# Voltage_sensor_UVW.net
KiCad netlist of a schematic drawn in Altium Designer
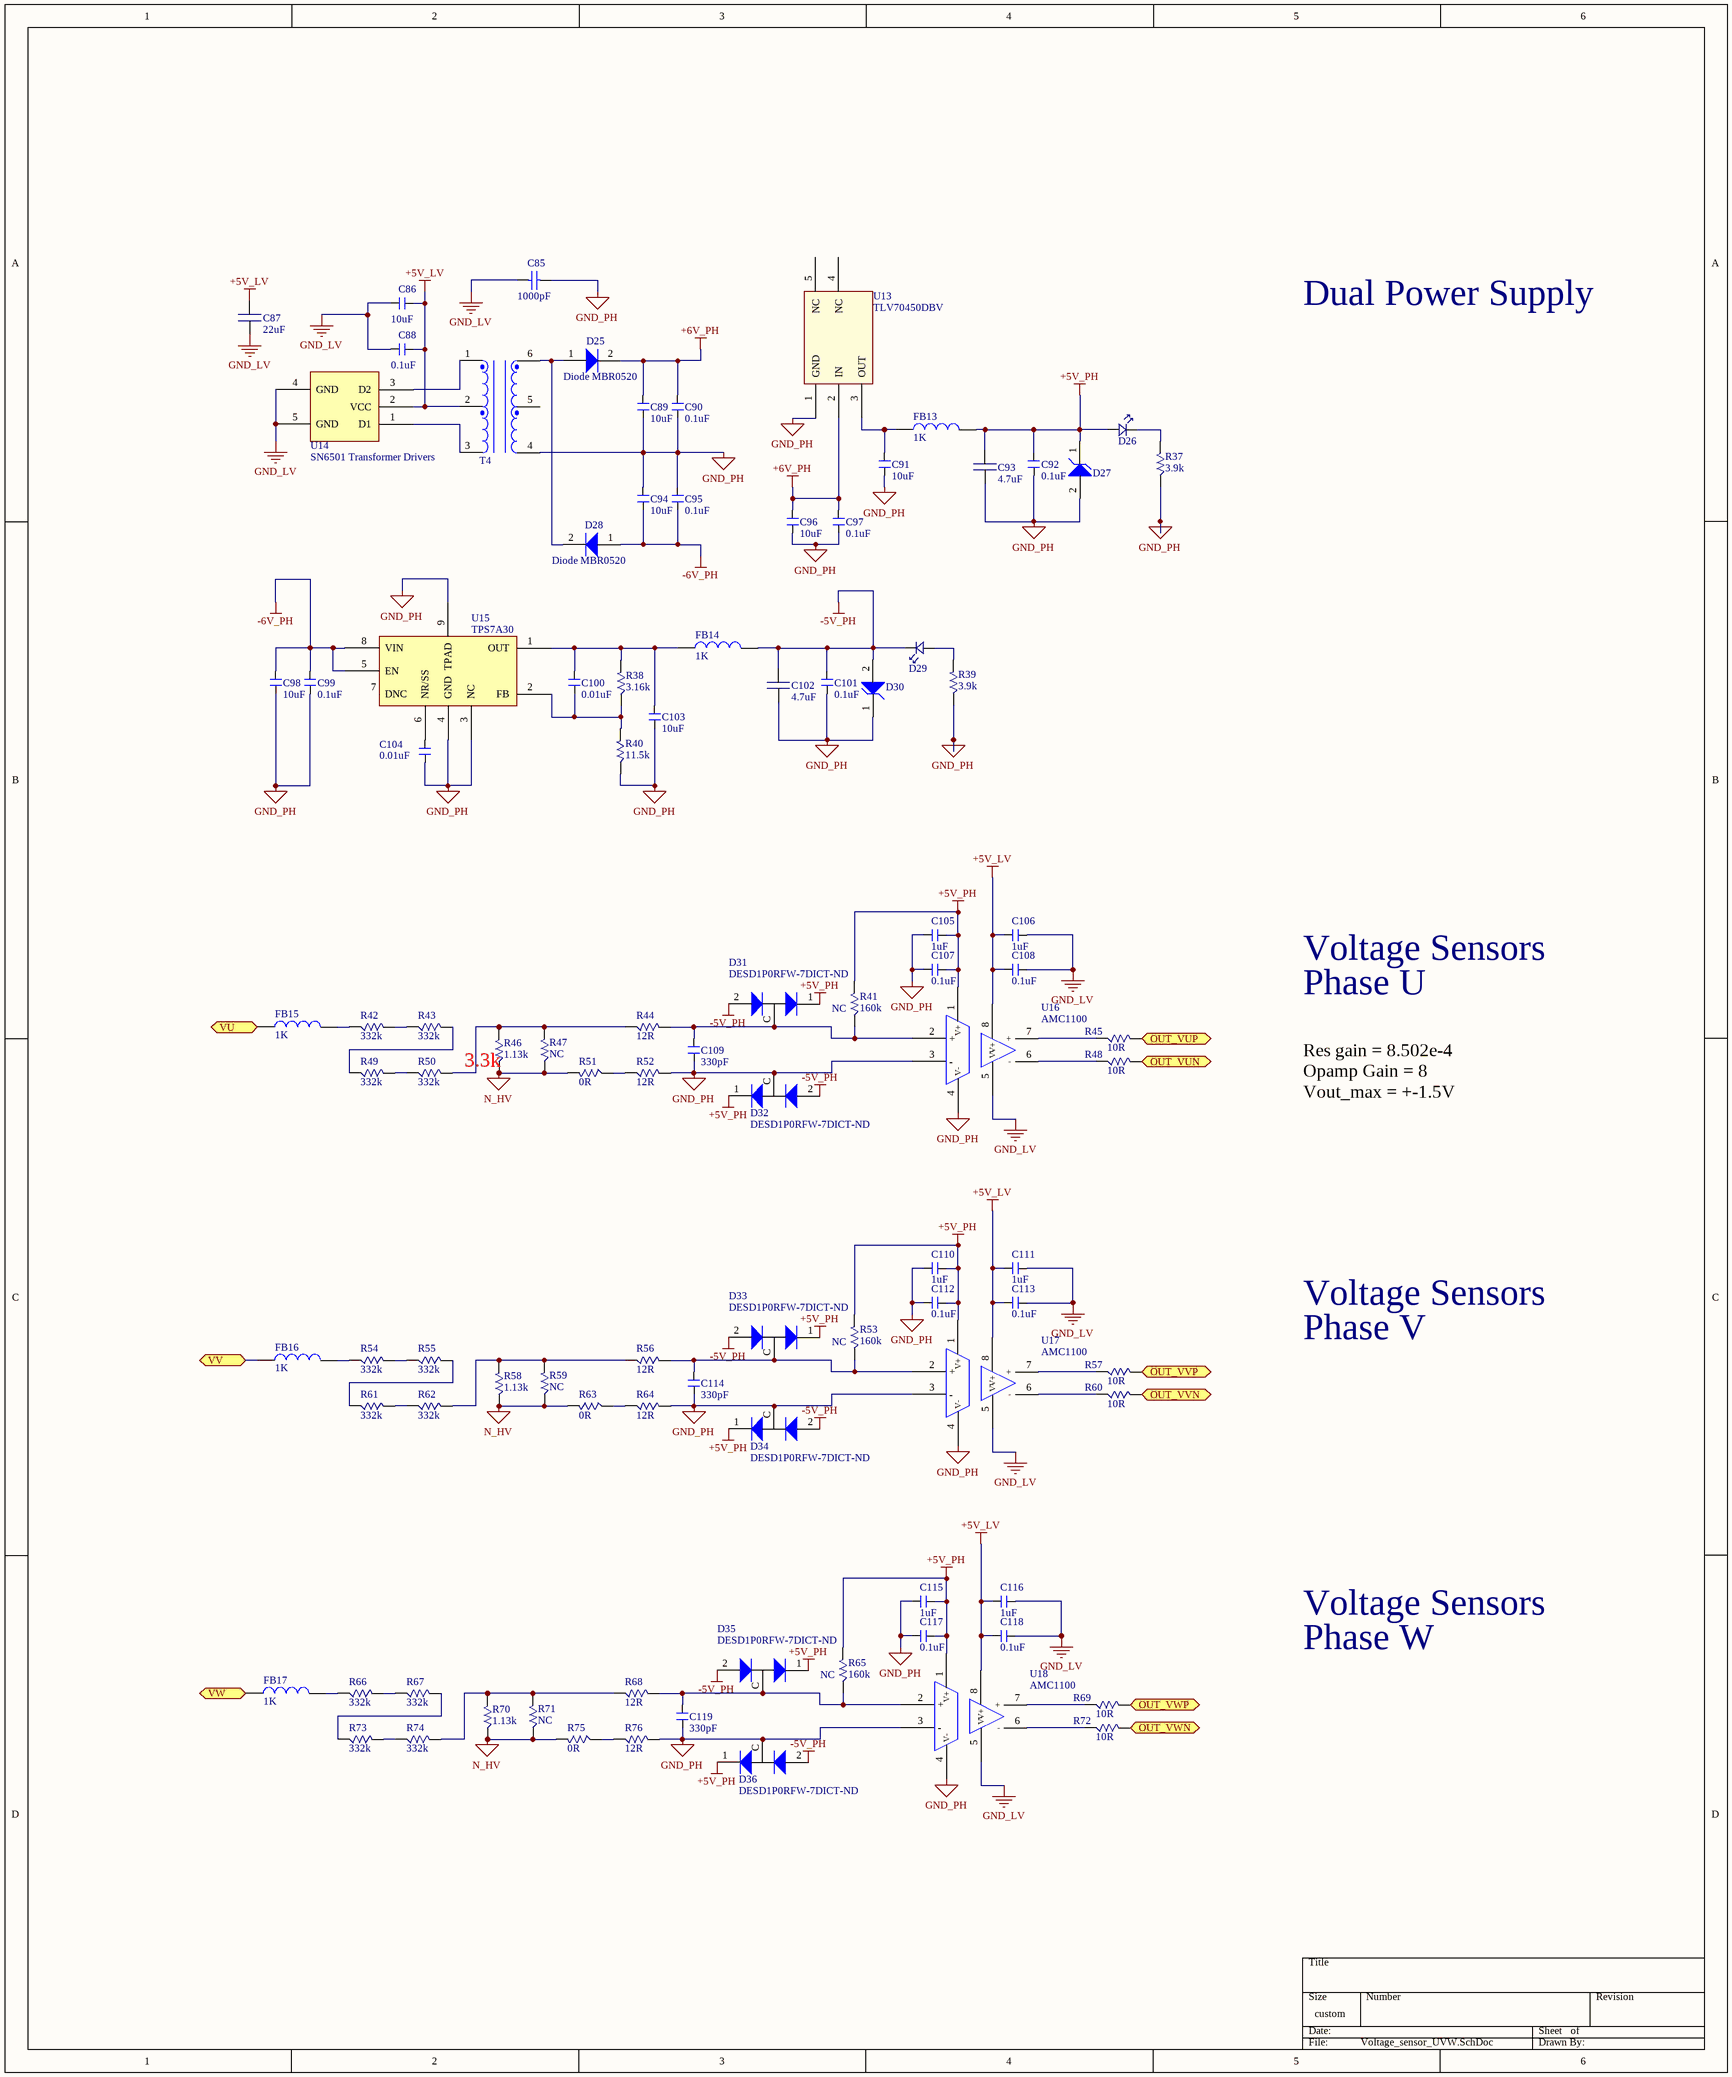
[diagram p0: Voltage_sensor_UVW.SchDoc]

(export (version "E")
  (design (tool "Eeschema 10.0.6"))
  (components
    (comp (ref "C85")
      (value "1000pF")
      (footprint "RAD-0.3")
      (description "CAP CER 1000PF 1KV Y5P RADIAL")
      (fields
        (field (name "PART") "1251PH-ND")
        (field (name "Comment") "Cap TH")
        (field (name "PUBLISHER") "Altium Limited")
      )
      (libsource (lib "Miscellaneous Devices") (part "Cap"))
    )
    (comp (ref "C86")
      (value "10uF")
      (footprint "0603 (1608 Metric)")
      (description "CAP CER 10UF 35V X5R 0805")
      (fields (field (name "PART") "490-10515-1-ND") (field (name "Comment") "Cap 0603_new"))
      (libsource (lib "Library_Microgrid") (part "Cap 0603_new"))
    )
    (comp (ref "C87")
      (value "22uF")
      (footprint "0805 (2012 metric)")
      (description "CAP CER 22UF 35V X5R 0805")
      (fields (field (name "PART") "445-14428-1-ND") (field (name "Comment") "Cap 0805"))
      (libsource (lib "Library_Microgrid") (part "Cap 0805"))
    )
    (comp (ref "C88")
      (value "0.1uF")
      (footprint "0603 (1608 Metric)")
      (description "CAP CER 0.1UF 50V Y5V 0603")
      (fields (field (name "PART") "311-1343-6-ND") (field (name "Comment") "Cap 0603_new"))
      (libsource (lib "Library_Microgrid") (part "Cap 0603_new"))
    )
    (comp (ref "C89")
      (value "10uF")
      (footprint "0603 (1608 Metric)")
      (description "CAP CER 10UF 35V X5R 0805")
      (fields (field (name "PART") "490-10515-1-ND") (field (name "Comment") "Cap 0603_new"))
      (libsource (lib "Library_Microgrid") (part "Cap 0603_new"))
    )
    (comp (ref "C90")
      (value "0.1uF")
      (footprint "0603 (1608 Metric)")
      (description "CAP CER 0.1UF 50V Y5V 0603")
      (fields (field (name "PART") "311-1343-6-ND") (field (name "Comment") "Cap 0603_new"))
      (libsource (lib "Library_Microgrid") (part "Cap 0603_new"))
    )
    (comp (ref "C91")
      (value "10uF")
      (footprint "0603 (1608 Metric)")
      (description "CAP CER 10UF 35V X5R 0805")
      (fields (field (name "PART") "490-10515-1-ND") (field (name "Comment") "Cap 0603_new"))
      (libsource (lib "Library_Microgrid") (part "Cap 0603_new"))
    )
    (comp (ref "C92")
      (value "0.1uF")
      (footprint "0603 (1608 Metric)")
      (description "CAP CER 0.1UF 50V Y5V 0603")
      (fields (field (name "PART") "311-1343-6-ND") (field (name "Comment") "Cap 0603_new"))
      (libsource (lib "Library_Microgrid") (part "Cap 0603_new"))
    )
    (comp (ref "C93")
      (value "4.7uF")
      (footprint "0805 (2012 metric)")
      (description "CAP CER 4.7UF 50V X5R 0805")
      (fields (field (name "PART") "445-5980-1-ND") (field (name "Comment") "Cap 0805"))
      (libsource (lib "Library_Microgrid") (part "Cap 0805"))
    )
    (comp (ref "C94")
      (value "10uF")
      (footprint "0603 (1608 Metric)")
      (description "CAP CER 10UF 35V X5R 0805")
      (fields (field (name "PART") "490-10515-1-ND") (field (name "Comment") "Cap 0603_new"))
      (libsource (lib "Library_Microgrid") (part "Cap 0603_new"))
    )
    (comp (ref "C95")
      (value "0.1uF")
      (footprint "0603 (1608 Metric)")
      (description "CAP CER 0.1UF 50V Y5V 0603")
      (fields (field (name "PART") "311-1343-6-ND") (field (name "Comment") "Cap 0603_new"))
      (libsource (lib "Library_Microgrid") (part "Cap 0603_new"))
    )
    (comp (ref "C96")
      (value "10uF")
      (footprint "0603 (1608 Metric)")
      (description "CAP CER 10UF 35V X5R 0805")
      (fields (field (name "PART") "490-10515-1-ND") (field (name "Comment") "Cap 0603_new"))
      (libsource (lib "Library_Microgrid") (part "Cap 0603_new"))
    )
    (comp (ref "C97")
      (value "0.1uF")
      (footprint "0603 (1608 Metric)")
      (description "CAP CER 0.1UF 50V Y5V 0603")
      (fields (field (name "PART") "311-1343-6-ND") (field (name "Comment") "Cap 0603_new"))
      (libsource (lib "Library_Microgrid") (part "Cap 0603_new"))
    )
    (comp (ref "C98")
      (value "10uF")
      (footprint "0603 (1608 Metric)")
      (description "CAP CER 10UF 35V X5R 0805")
      (fields (field (name "PART") "490-10515-1-ND") (field (name "Comment") "Cap 0603_new"))
      (libsource (lib "Library_Microgrid") (part "Cap 0603_new"))
    )
    (comp (ref "C99")
      (value "0.1uF")
      (footprint "0603 (1608 Metric)")
      (description "CAP CER 0.1UF 50V Y5V 0603")
      (fields (field (name "PART") "311-1343-6-ND") (field (name "Comment") "Cap 0603_new"))
      (libsource (lib "Library_Microgrid") (part "Cap 0603_new"))
    )
    (comp (ref "C100")
      (value "0.01uF")
      (footprint "0603 (1608 Metric)")
      (description "CAP CER 10000PF 100V X7R 0603")
      (fields (field (name "PART") "478-7418-1-ND") (field (name "Comment") "Cap 0603_new"))
      (libsource (lib "Library_Microgrid") (part "Cap 0603_new"))
    )
    (comp (ref "C101")
      (value "0.1uF")
      (footprint "0603 (1608 Metric)")
      (description "CAP CER 0.1UF 50V Y5V 0603")
      (fields (field (name "PART") "311-1343-6-ND") (field (name "Comment") "Cap 0603_new"))
      (libsource (lib "Library_Microgrid") (part "Cap 0603_new"))
    )
    (comp (ref "C102")
      (value "4.7uF")
      (footprint "0805 (2012 metric)")
      (description "CAP CER 4.7UF 50V X5R 0805")
      (fields (field (name "PART") "445-5980-1-ND") (field (name "Comment") "Cap 0805"))
      (libsource (lib "Library_Microgrid") (part "Cap 0805"))
    )
    (comp (ref "C103")
      (value "10uF")
      (footprint "0603 (1608 Metric)")
      (description "CAP CER 10UF 35V X5R 0805")
      (fields (field (name "PART") "490-10515-1-ND") (field (name "Comment") "Cap 0603_new"))
      (libsource (lib "Library_Microgrid") (part "Cap 0603_new"))
    )
    (comp (ref "C104")
      (value "0.01uF")
      (footprint "0603 (1608 Metric)")
      (description "CAP CER 10000PF 100V X7R 0603")
      (fields (field (name "PART") "478-7418-1-ND") (field (name "Comment") "Cap 0603_new"))
      (libsource (lib "Library_Microgrid") (part "Cap 0603_new"))
    )
    (comp (ref "C105")
      (value "1uF")
      (footprint "0603 (1608 Metric)")
      (description "CAP CER 1UF 50V X5R 0603")
      (fields (field (name "PART") "1276-1860-1-ND") (field (name "Comment") "Cap 0603_new"))
      (libsource (lib "Library_Microgrid") (part "Cap 0603_new"))
    )
    (comp (ref "C106")
      (value "1uF")
      (footprint "0603 (1608 Metric)")
      (description "CAP CER 1UF 50V X5R 0603")
      (fields (field (name "PART") "1276-1860-1-ND") (field (name "Comment") "Cap 0603_new"))
      (libsource (lib "Library_Microgrid") (part "Cap 0603_new"))
    )
    (comp (ref "C107")
      (value "0.1uF")
      (footprint "0603 (1608 Metric)")
      (description "CAP CER 0.1UF 50V Y5V 0603")
      (fields (field (name "PART") "311-1343-6-ND") (field (name "Comment") "Cap 0603_new"))
      (libsource (lib "Library_Microgrid") (part "Cap 0603_new"))
    )
    (comp (ref "C108")
      (value "0.1uF")
      (footprint "0603 (1608 Metric)")
      (description "CAP CER 0.1UF 50V Y5V 0603")
      (fields (field (name "PART") "311-1343-6-ND") (field (name "Comment") "Cap 0603_new"))
      (libsource (lib "Library_Microgrid") (part "Cap 0603_new"))
    )
    (comp (ref "C109")
      (value "330pF")
      (footprint "0603 (1608 Metric)")
      (description "CAP CER 330PF 50V C0G 0603")
      (fields (field (name "PART") "445-7033-2-ND") (field (name "Comment") "Cap 0603_new"))
      (libsource (lib "Library_Microgrid") (part "Cap 0603_new"))
    )
    (comp (ref "C110")
      (value "1uF")
      (footprint "0603 (1608 Metric)")
      (description "CAP CER 1UF 50V X5R 0603")
      (fields (field (name "PART") "1276-1860-1-ND") (field (name "Comment") "Cap 0603_new"))
      (libsource (lib "Library_Microgrid") (part "Cap 0603_new"))
    )
    (comp (ref "C111")
      (value "1uF")
      (footprint "0603 (1608 Metric)")
      (description "CAP CER 1UF 50V X5R 0603")
      (fields (field (name "PART") "1276-1860-1-ND") (field (name "Comment") "Cap 0603_new"))
      (libsource (lib "Library_Microgrid") (part "Cap 0603_new"))
    )
    (comp (ref "C112")
      (value "0.1uF")
      (footprint "0603 (1608 Metric)")
      (description "CAP CER 0.1UF 50V Y5V 0603")
      (fields (field (name "PART") "311-1343-6-ND") (field (name "Comment") "Cap 0603_new"))
      (libsource (lib "Library_Microgrid") (part "Cap 0603_new"))
    )
    (comp (ref "C113")
      (value "0.1uF")
      (footprint "0603 (1608 Metric)")
      (description "CAP CER 0.1UF 50V Y5V 0603")
      (fields (field (name "PART") "311-1343-6-ND") (field (name "Comment") "Cap 0603_new"))
      (libsource (lib "Library_Microgrid") (part "Cap 0603_new"))
    )
    (comp (ref "C114")
      (value "330pF")
      (footprint "0603 (1608 Metric)")
      (description "CAP CER 330PF 50V C0G 0603")
      (fields (field (name "PART") "445-7033-2-ND") (field (name "Comment") "Cap 0603_new"))
      (libsource (lib "Library_Microgrid") (part "Cap 0603_new"))
    )
    (comp (ref "C115")
      (value "1uF")
      (footprint "0603 (1608 Metric)")
      (description "CAP CER 1UF 50V X5R 0603")
      (fields (field (name "PART") "1276-1860-1-ND") (field (name "Comment") "Cap 0603_new"))
      (libsource (lib "Library_Microgrid") (part "Cap 0603_new"))
    )
    (comp (ref "C116")
      (value "1uF")
      (footprint "0603 (1608 Metric)")
      (description "CAP CER 1UF 50V X5R 0603")
      (fields (field (name "PART") "1276-1860-1-ND") (field (name "Comment") "Cap 0603_new"))
      (libsource (lib "Library_Microgrid") (part "Cap 0603_new"))
    )
    (comp (ref "C117")
      (value "0.1uF")
      (footprint "0603 (1608 Metric)")
      (description "CAP CER 0.1UF 50V Y5V 0603")
      (fields (field (name "PART") "311-1343-6-ND") (field (name "Comment") "Cap 0603_new"))
      (libsource (lib "Library_Microgrid") (part "Cap 0603_new"))
    )
    (comp (ref "C118")
      (value "0.1uF")
      (footprint "0603 (1608 Metric)")
      (description "CAP CER 0.1UF 50V Y5V 0603")
      (fields (field (name "PART") "311-1343-6-ND") (field (name "Comment") "Cap 0603_new"))
      (libsource (lib "Library_Microgrid") (part "Cap 0603_new"))
    )
    (comp (ref "C119")
      (value "330pF")
      (footprint "0603 (1608 Metric)")
      (description "CAP CER 330PF 50V C0G 0603")
      (fields (field (name "PART") "445-7033-2-ND") (field (name "Comment") "Cap 0603_new"))
      (libsource (lib "Library_Microgrid") (part "Cap 0603_new"))
    )
    (comp (ref "D25")
      (value "Diode MBR0520")
      (footprint "SOD-123")
      (description "DIODE SCHOTTKY 20V 500MA SOD123")
      (fields (field (name "PART") "MBR0520LT1GOSCT-ND"))
      (libsource (lib "Library_Microgrid") (part "Diode MBR0520"))
    )
    (comp (ref "D26")
      (value "LED")
      (footprint "0805 (2012 Metric) Diode")
      (description "LED 0805")
      (libsource (lib "Library_Microgrid") (part "LED"))
    )
    (comp (ref "D27")
      (value "*")
      (footprint "POWERDI")
      (description "DIODE ZENER POWERDI123")
      (fields (field (name "PART") "MMSZ5228B-FDICT-ND"))
      (libsource (lib "Library_Microgrid") (part "Diode Zener POWERDI123"))
    )
    (comp (ref "D28")
      (value "Diode MBR0520")
      (footprint "SOD-123")
      (description "DIODE SCHOTTKY 20V 500MA SOD123")
      (fields (field (name "PART") "MBR0520LT1GOSCT-ND"))
      (libsource (lib "Library_Microgrid") (part "Diode MBR0520"))
    )
    (comp (ref "D29")
      (value "LED")
      (footprint "0805 (2012 Metric) Diode")
      (description "LED 0805")
      (libsource (lib "Library_Microgrid") (part "LED"))
    )
    (comp (ref "D30")
      (value "*")
      (footprint "POWERDI")
      (description "DIODE ZENER POWERDI123")
      (fields (field (name "PART") "MMSZ5228B-FDICT-ND"))
      (libsource (lib "Library_Microgrid") (part "Diode Zener POWERDI123"))
    )
    (comp (ref "D31")
      (value "TVS - Diodes")
      (footprint "SOT323_ESD")
      (description "TVS DIODE 70VWM 8VC SOT323")
      (fields (field (name "PART") "DESD1P0RFW-7DICT-ND"))
      (libsource (lib "Library_Microgrid") (part "Diode_ESD"))
    )
    (comp (ref "D32")
      (value "TVS - Diodes")
      (footprint "SOT323_ESD")
      (description "TVS DIODE 70VWM 8VC SOT323")
      (fields (field (name "PART") "DESD1P0RFW-7DICT-ND"))
      (libsource (lib "Library_Microgrid") (part "Diode_ESD"))
    )
    (comp (ref "D33")
      (value "TVS - Diodes")
      (footprint "SOT323_ESD")
      (description "TVS DIODE 70VWM 8VC SOT323")
      (fields (field (name "PART") "DESD1P0RFW-7DICT-ND"))
      (libsource (lib "Library_Microgrid") (part "Diode_ESD"))
    )
    (comp (ref "D34")
      (value "TVS - Diodes")
      (footprint "SOT323_ESD")
      (description "TVS DIODE 70VWM 8VC SOT323")
      (fields (field (name "PART") "DESD1P0RFW-7DICT-ND"))
      (libsource (lib "Library_Microgrid") (part "Diode_ESD"))
    )
    (comp (ref "D35")
      (value "TVS - Diodes")
      (footprint "SOT323_ESD")
      (description "TVS DIODE 70VWM 8VC SOT323")
      (fields (field (name "PART") "DESD1P0RFW-7DICT-ND"))
      (libsource (lib "Library_Microgrid") (part "Diode_ESD"))
    )
    (comp (ref "D36")
      (value "TVS - Diodes")
      (footprint "SOT323_ESD")
      (description "TVS DIODE 70VWM 8VC SOT323")
      (fields (field (name "PART") "DESD1P0RFW-7DICT-ND"))
      (libsource (lib "Library_Microgrid") (part "Diode_ESD"))
    )
    (comp (ref "FB13")
      (value "1K")
      (footprint "0603 (1608 Metric)")
      (description "FERRITE BEAD 1 KOHM 0603 1LN")
      (fields (field (name "PART") "445-8672-1-ND") (field (name "Comment") "Ferrite bead"))
      (libsource (lib "Library_Microgrid") (part "Ferrite bead"))
    )
    (comp (ref "FB14")
      (value "1K")
      (footprint "0603 (1608 Metric)")
      (description "FERRITE BEAD 1 KOHM 0603 1LN")
      (fields (field (name "PART") "445-8672-1-ND") (field (name "Comment") "Ferrite bead"))
      (libsource (lib "Library_Microgrid") (part "Ferrite bead"))
    )
    (comp (ref "FB15")
      (value "1K")
      (footprint "0603 (1608 Metric)")
      (description "FERRITE BEAD 1 KOHM 0603 1LN")
      (fields (field (name "PART") "445-8672-1-ND") (field (name "Comment") "Ferrite bead"))
      (libsource (lib "Library_Microgrid") (part "Ferrite bead"))
    )
    (comp (ref "FB16")
      (value "1K")
      (footprint "0603 (1608 Metric)")
      (description "FERRITE BEAD 1 KOHM 0603 1LN")
      (fields (field (name "PART") "445-8672-1-ND") (field (name "Comment") "Ferrite bead"))
      (libsource (lib "Library_Microgrid") (part "Ferrite bead"))
    )
    (comp (ref "FB17")
      (value "1K")
      (footprint "0603 (1608 Metric)")
      (description "FERRITE BEAD 1 KOHM 0603 1LN")
      (fields (field (name "PART") "445-8672-1-ND") (field (name "Comment") "Ferrite bead"))
      (libsource (lib "Library_Microgrid") (part "Ferrite bead"))
    )
    (comp (ref "R37")
      (value "3.9k")
      (footprint "0603 (1608 Metric)")
      (description "RES SMD 3.9K OHM 5% 1/10W 0603")
      (fields (field (name "PART") "541-3.9KGCT-ND") (field (name "Comment") "Resistor 0603"))
      (libsource (lib "Library_Microgrid") (part "Resistor 0603"))
    )
    (comp (ref "R38")
      (value "3.16k")
      (footprint "0603 (1608 Metric)")
      (description "RES SMD 3.16K OHM 1% 1/10W 0603")
      (fields (field (name "PART") "311-3.16KHRCT-ND") (field (name "Comment") "Resistor 0603"))
      (libsource (lib "Library_Microgrid") (part "Resistor 0603"))
    )
    (comp (ref "R39")
      (value "3.9k")
      (footprint "0603 (1608 Metric)")
      (description "RES SMD 3.9K OHM 5% 1/10W 0603")
      (fields (field (name "PART") "541-3.9KGCT-ND") (field (name "Comment") "Resistor 0603"))
      (libsource (lib "Library_Microgrid") (part "Resistor 0603"))
    )
    (comp (ref "R40")
      (value "11.5k")
      (footprint "0603 (1608 Metric)")
      (description "RES SMD 11.5K OHM 1% 1/10W 0603")
      (fields (field (name "PART") "541-11.5KHCT-ND") (field (name "Comment") "Resistor 0603"))
      (libsource (lib "Library_Microgrid") (part "Resistor 0603"))
    )
    (comp (ref "R41")
      (value "NC")
      (footprint "0603 (1608 Metric)")
      (description "Resistor 0603")
      (fields (field (name "ALTIUM_VALUE") "160k"))
      (libsource (lib "Library_Microgrid") (part "Resistor 0603"))
    )
    (comp (ref "R42")
      (value "332k")
      (footprint "1206")
      (description "RES SMD 332K OHM 0.1% 1/4W 1206")
      (fields (field (name "PART") "RG32P332KBCT-ND") (field (name "Comment") "Resistor 1206"))
      (libsource (lib "Library_Microgrid") (part "Resistor 1206"))
    )
    (comp (ref "R43")
      (value "332k")
      (footprint "1206")
      (description "RES SMD 332K OHM 0.1% 1/4W 1206")
      (fields (field (name "PART") "RG32P332KBCT-ND") (field (name "Comment") "Resistor 1206"))
      (libsource (lib "Library_Microgrid") (part "Resistor 1206"))
    )
    (comp (ref "R44")
      (value "12R")
      (footprint "1206")
      (description "12 Ohm ±0.5% 0.25W, 1/4W Chip Resistor 1206")
      (fields (field (name "PART") "311-2961-1-ND") (field (name "Comment") "Resistor 1206"))
      (libsource (lib "Library_Microgrid") (part "Resistor 1206"))
    )
    (comp (ref "R45")
      (value "10R")
      (footprint "0603 (1608 Metric)")
      (description "RES SMD 10 OHM 0.05% 1/10W 0603")
      (fields (field (name "PART") "RNCF0603AKT10R0CT-ND") (field (name "Comment") "Resistor 0603"))
      (libsource (lib "Library_Microgrid") (part "Resistor 0603"))
    )
    (comp (ref "R46")
      (value "1.13k")
      (footprint "1206")
      (description "RES SMD 1.13K OHM 0.1% 1/4W 1206")
      (fields (field (name "PART") "P1.13KBCCT-ND") (field (name "Comment") "Resistor 1206"))
      (libsource (lib "Library_Microgrid") (part "Resistor 1206"))
    )
    (comp (ref "R47")
      (value "NC")
      (footprint "1206")
      (fields (field (name "Comment") "Resistor 1206"))
      (libsource (lib "Library_Microgrid") (part "Resistor 1206"))
    )
    (comp (ref "R48")
      (value "10R")
      (footprint "0603 (1608 Metric)")
      (description "RES SMD 10 OHM 0.05% 1/10W 0603")
      (fields (field (name "PART") "RNCF0603AKT10R0CT-ND") (field (name "Comment") "Resistor 0603"))
      (libsource (lib "Library_Microgrid") (part "Resistor 0603"))
    )
    (comp (ref "R49")
      (value "332k")
      (footprint "1206")
      (description "RES SMD 332K OHM 0.1% 1/4W 1206")
      (fields (field (name "PART") "RG32P332KBCT-ND") (field (name "Comment") "Resistor 1206"))
      (libsource (lib "Library_Microgrid") (part "Resistor 1206"))
    )
    (comp (ref "R50")
      (value "332k")
      (footprint "1206")
      (description "RES SMD 332K OHM 0.1% 1/4W 1206")
      (fields (field (name "PART") "RG32P332KBCT-ND") (field (name "Comment") "Resistor 1206"))
      (libsource (lib "Library_Microgrid") (part "Resistor 1206"))
    )
    (comp (ref "R51")
      (value "0R")
      (footprint "0603 (1608 Metric)")
      (fields (field (name "Comment") "Resistor 0603"))
      (libsource (lib "Library_Microgrid") (part "Resistor 0603"))
    )
    (comp (ref "R52")
      (value "12R")
      (footprint "1206")
      (description "12 Ohm ±0.5% 0.25W, 1/4W Chip Resistor 1206")
      (fields (field (name "PART") "311-2961-1-ND") (field (name "Comment") "Resistor 1206"))
      (libsource (lib "Library_Microgrid") (part "Resistor 1206"))
    )
    (comp (ref "R53")
      (value "NC")
      (footprint "0603 (1608 Metric)")
      (description "Resistor 0603")
      (fields (field (name "ALTIUM_VALUE") "160k"))
      (libsource (lib "Library_Microgrid") (part "Resistor 0603"))
    )
    (comp (ref "R54")
      (value "332k")
      (footprint "1206")
      (description "RES SMD 332K OHM 0.1% 1/4W 1206")
      (fields (field (name "PART") "RG32P332KBCT-ND") (field (name "Comment") "Resistor 1206"))
      (libsource (lib "Library_Microgrid") (part "Resistor 1206"))
    )
    (comp (ref "R55")
      (value "332k")
      (footprint "1206")
      (description "RES SMD 332K OHM 0.1% 1/4W 1206")
      (fields (field (name "PART") "RG32P332KBCT-ND") (field (name "Comment") "Resistor 1206"))
      (libsource (lib "Library_Microgrid") (part "Resistor 1206"))
    )
    (comp (ref "R56")
      (value "12R")
      (footprint "1206")
      (description "12 Ohm ±0.5% 0.25W, 1/4W Chip Resistor 1206")
      (fields (field (name "PART") "311-2961-1-ND") (field (name "Comment") "Resistor 1206"))
      (libsource (lib "Library_Microgrid") (part "Resistor 1206"))
    )
    (comp (ref "R57")
      (value "10R")
      (footprint "0603 (1608 Metric)")
      (description "RES SMD 10 OHM 0.05% 1/10W 0603")
      (fields (field (name "PART") "RNCF0603AKT10R0CT-ND") (field (name "Comment") "Resistor 0603"))
      (libsource (lib "Library_Microgrid") (part "Resistor 0603"))
    )
    (comp (ref "R58")
      (value "1.13k")
      (footprint "1206")
      (description "RES SMD 1.13K OHM 0.1% 1/4W 1206")
      (fields (field (name "PART") "P1.13KBCCT-ND") (field (name "Comment") "Resistor 1206"))
      (libsource (lib "Library_Microgrid") (part "Resistor 1206"))
    )
    (comp (ref "R59")
      (value "NC")
      (footprint "1206")
      (fields (field (name "Comment") "Resistor 1206"))
      (libsource (lib "Library_Microgrid") (part "Resistor 1206"))
    )
    (comp (ref "R60")
      (value "10R")
      (footprint "0603 (1608 Metric)")
      (description "RES SMD 10 OHM 0.05% 1/10W 0603")
      (fields (field (name "PART") "RNCF0603AKT10R0CT-ND") (field (name "Comment") "Resistor 0603"))
      (libsource (lib "Library_Microgrid") (part "Resistor 0603"))
    )
    (comp (ref "R61")
      (value "332k")
      (footprint "1206")
      (description "RES SMD 332K OHM 0.1% 1/4W 1206")
      (fields (field (name "PART") "RG32P332KBCT-ND") (field (name "Comment") "Resistor 1206"))
      (libsource (lib "Library_Microgrid") (part "Resistor 1206"))
    )
    (comp (ref "R62")
      (value "332k")
      (footprint "1206")
      (description "RES SMD 332K OHM 0.1% 1/4W 1206")
      (fields (field (name "PART") "RG32P332KBCT-ND") (field (name "Comment") "Resistor 1206"))
      (libsource (lib "Library_Microgrid") (part "Resistor 1206"))
    )
    (comp (ref "R63")
      (value "0R")
      (footprint "0603 (1608 Metric)")
      (fields (field (name "Comment") "Resistor 0603"))
      (libsource (lib "Library_Microgrid") (part "Resistor 0603"))
    )
    (comp (ref "R64")
      (value "12R")
      (footprint "1206")
      (description "12 Ohm ±0.5% 0.25W, 1/4W Chip Resistor 1206")
      (fields (field (name "PART") "311-2961-1-ND") (field (name "Comment") "Resistor 1206"))
      (libsource (lib "Library_Microgrid") (part "Resistor 1206"))
    )
    (comp (ref "R65")
      (value "NC")
      (footprint "0603 (1608 Metric)")
      (description "Resistor 0603")
      (fields (field (name "ALTIUM_VALUE") "160k"))
      (libsource (lib "Library_Microgrid") (part "Resistor 0603"))
    )
    (comp (ref "R66")
      (value "332k")
      (footprint "1206")
      (description "RES SMD 332K OHM 0.1% 1/4W 1206")
      (fields (field (name "PART") "RG32P332KBCT-ND") (field (name "Comment") "Resistor 1206"))
      (libsource (lib "Library_Microgrid") (part "Resistor 1206"))
    )
    (comp (ref "R67")
      (value "332k")
      (footprint "1206")
      (description "RES SMD 332K OHM 0.1% 1/4W 1206")
      (fields (field (name "PART") "RG32P332KBCT-ND") (field (name "Comment") "Resistor 1206"))
      (libsource (lib "Library_Microgrid") (part "Resistor 1206"))
    )
    (comp (ref "R68")
      (value "12R")
      (footprint "1206")
      (description "12 Ohm ±0.5% 0.25W, 1/4W Chip Resistor 1206")
      (fields (field (name "PART") "311-2961-1-ND") (field (name "Comment") "Resistor 1206"))
      (libsource (lib "Library_Microgrid") (part "Resistor 1206"))
    )
    (comp (ref "R69")
      (value "10R")
      (footprint "0603 (1608 Metric)")
      (description "RES SMD 10 OHM 0.05% 1/10W 0603")
      (fields (field (name "PART") "RNCF0603AKT10R0CT-ND") (field (name "Comment") "Resistor 0603"))
      (libsource (lib "Library_Microgrid") (part "Resistor 0603"))
    )
    (comp (ref "R70")
      (value "1.13k")
      (footprint "1206")
      (description "RES SMD 1.13K OHM 0.1% 1/4W 1206")
      (fields (field (name "PART") "P1.13KBCCT-ND") (field (name "Comment") "Resistor 1206"))
      (libsource (lib "Library_Microgrid") (part "Resistor 1206"))
    )
    (comp (ref "R71")
      (value "NC")
      (footprint "1206")
      (fields (field (name "Comment") "Resistor 1206"))
      (libsource (lib "Library_Microgrid") (part "Resistor 1206"))
    )
    (comp (ref "R72")
      (value "10R")
      (footprint "0603 (1608 Metric)")
      (description "RES SMD 10 OHM 0.05% 1/10W 0603")
      (fields (field (name "PART") "RNCF0603AKT10R0CT-ND") (field (name "Comment") "Resistor 0603"))
      (libsource (lib "Library_Microgrid") (part "Resistor 0603"))
    )
    (comp (ref "R73")
      (value "332k")
      (footprint "1206")
      (description "RES SMD 332K OHM 0.1% 1/4W 1206")
      (fields (field (name "PART") "RG32P332KBCT-ND") (field (name "Comment") "Resistor 1206"))
      (libsource (lib "Library_Microgrid") (part "Resistor 1206"))
    )
    (comp (ref "R74")
      (value "332k")
      (footprint "1206")
      (description "RES SMD 332K OHM 0.1% 1/4W 1206")
      (fields (field (name "PART") "RG32P332KBCT-ND") (field (name "Comment") "Resistor 1206"))
      (libsource (lib "Library_Microgrid") (part "Resistor 1206"))
    )
    (comp (ref "R75")
      (value "0R")
      (footprint "0603 (1608 Metric)")
      (fields (field (name "Comment") "Resistor 0603"))
      (libsource (lib "Library_Microgrid") (part "Resistor 0603"))
    )
    (comp (ref "R76")
      (value "12R")
      (footprint "1206")
      (description "12 Ohm ±0.5% 0.25W, 1/4W Chip Resistor 1206")
      (fields (field (name "PART") "311-2961-1-ND") (field (name "Comment") "Resistor 1206"))
      (libsource (lib "Library_Microgrid") (part "Resistor 1206"))
    )
    (comp (ref "T4")
      (value "750313769")
      (footprint "Xmr SN6501")
      (description "TRANSFORMER SMD TR1.7 SN6501")
      (fields (field (name "PART") "1297-1107-1-ND"))
      (libsource (lib "Library_Microgrid") (part "750313769"))
    )
    (comp (ref "U13")
      (value "TLV70450DBV")
      (footprint "SOT23-5")
      (description "IC REG LDO 5V 0.15A SOT23-5")
      (fields (field (name "PART") "296-39287-1-ND"))
      (libsource (lib "Library_Microgrid") (part "TLV70450DBV"))
    )
    (comp (ref "U14")
      (value "SN6501 Transformer Drivers")
      (footprint "SOT23-5")
      (description "IC REG CONV PWR SUPPLIES SOT23-5")
      (fields (field (name "PART") "296-37700-1-ND"))
      (libsource (lib "Library_Microgrid") (part "SN6501"))
    )
    (comp (ref "U15")
      (value "TPS7A30")
      (footprint "8-TSSOP")
      (description "IC REG LDO NEG ADJ 0.2A 8MSOP")
      (fields (field (name "PART") "296-27750-1-ND"))
      (libsource (lib "Library_Microgrid") (part "TPS7A30"))
    )
    (comp (ref "U16")
      (value "AMC1100")
      (footprint "SOIC8")
      (description "IC OPAMP ISOLATION 100KHZ 8SOIC")
      (fields (field (name "PART") "296-38822-5-ND"))
      (libsource (lib "Library_Microgrid") (part "AMC1100"))
    )
    (comp (ref "U17")
      (value "AMC1100")
      (footprint "SOIC8")
      (description "IC OPAMP ISOLATION 100KHZ 8SOIC")
      (fields (field (name "PART") "296-38822-5-ND"))
      (libsource (lib "Library_Microgrid") (part "AMC1100"))
    )
    (comp (ref "U18")
      (value "AMC1100")
      (footprint "SOIC8")
      (description "IC OPAMP ISOLATION 100KHZ 8SOIC")
      (fields (field (name "PART") "296-38822-5-ND"))
      (libsource (lib "Library_Microgrid") (part "AMC1100"))
    )
  )
  (nets
    (net (code "1") (name "+5V_LV") (class "Default")
      (node (ref "C106") (pin "1") (pinfunction "OUT_1") (pintype "passive"))
      (node (ref "C108") (pin "1") (pinfunction "OUT_1") (pintype "passive"))
      (node (ref "C111") (pin "1") (pinfunction "OUT_1") (pintype "passive"))
      (node (ref "C113") (pin "1") (pinfunction "OUT_1") (pintype "passive"))
      (node (ref "C116") (pin "1") (pinfunction "OUT_1") (pintype "passive"))
      (node (ref "C118") (pin "1") (pinfunction "OUT_1") (pintype "passive"))
      (node (ref "C86") (pin "2") (pinfunction "OUT_2") (pintype "passive"))
      (node (ref "C87") (pin "2") (pinfunction "OUT_2") (pintype "passive"))
      (node (ref "C88") (pin "2") (pinfunction "OUT_2") (pintype "passive"))
      (node (ref "T4") (pin "2") (pinfunction "1_2") (pintype "passive"))
      (node (ref "U14") (pin "2") (pinfunction "VCC_2") (pintype "passive"))
      (node (ref "U16") (pin "8") (pinfunction "V+_8") (pintype "passive"))
      (node (ref "U17") (pin "8") (pinfunction "V+_8") (pintype "passive"))
      (node (ref "U18") (pin "8") (pinfunction "V+_8") (pintype "passive"))
    )
    (net (code "2") (name "+5V_PH") (class "Default")
      (node (ref "C105") (pin "2") (pinfunction "OUT_2") (pintype "passive"))
      (node (ref "C107") (pin "2") (pinfunction "OUT_2") (pintype "passive"))
      (node (ref "C110") (pin "2") (pinfunction "OUT_2") (pintype "passive"))
      (node (ref "C112") (pin "2") (pinfunction "OUT_2") (pintype "passive"))
      (node (ref "C115") (pin "2") (pinfunction "OUT_2") (pintype "passive"))
      (node (ref "C117") (pin "2") (pinfunction "OUT_2") (pintype "passive"))
      (node (ref "C92") (pin "2") (pinfunction "OUT_2") (pintype "passive"))
      (node (ref "C93") (pin "2") (pinfunction "OUT_2") (pintype "passive"))
      (node (ref "D26") (pin "A") (pinfunction "A_A") (pintype "passive"))
      (node (ref "D27") (pin "1") (pinfunction "Anode_1") (pintype "passive"))
      (node (ref "D31") (pin "1") (pinfunction "Anode_1") (pintype "passive"))
      (node (ref "D32") (pin "1") (pinfunction "Anode_1") (pintype "passive"))
      (node (ref "D33") (pin "1") (pinfunction "Anode_1") (pintype "passive"))
      (node (ref "D34") (pin "1") (pinfunction "Anode_1") (pintype "passive"))
      (node (ref "D35") (pin "1") (pinfunction "Anode_1") (pintype "passive"))
      (node (ref "D36") (pin "1") (pinfunction "Anode_1") (pintype "passive"))
      (node (ref "FB13") (pin "2") (pinfunction "OUT_2") (pintype "passive"))
      (node (ref "R41") (pin "2") (pinfunction "A_2") (pintype "passive"))
      (node (ref "R53") (pin "2") (pinfunction "A_2") (pintype "passive"))
      (node (ref "R65") (pin "2") (pinfunction "A_2") (pintype "passive"))
      (node (ref "U16") (pin "1") (pinfunction "V+_1") (pintype "passive"))
      (node (ref "U17") (pin "1") (pinfunction "V+_1") (pintype "passive"))
      (node (ref "U18") (pin "1") (pinfunction "V+_1") (pintype "passive"))
    )
    (net (code "3") (name "+6V_PH") (class "Default")
      (node (ref "C89") (pin "2") (pinfunction "OUT_2") (pintype "passive"))
      (node (ref "C90") (pin "2") (pinfunction "OUT_2") (pintype "passive"))
      (node (ref "C96") (pin "2") (pinfunction "OUT_2") (pintype "passive"))
      (node (ref "C97") (pin "2") (pinfunction "OUT_2") (pintype "passive"))
      (node (ref "D25") (pin "2") (pinfunction "Anode_2") (pintype "passive"))
      (node (ref "U13") (pin "2") (pinfunction "IN_2") (pintype "passive"))
    )
    (net (code "4") (name "-5V_PH") (class "Default")
      (node (ref "C101") (pin "2") (pinfunction "OUT_2") (pintype "passive"))
      (node (ref "C102") (pin "2") (pinfunction "OUT_2") (pintype "passive"))
      (node (ref "D29") (pin "K") (pinfunction "K_K") (pintype "passive"))
      (node (ref "D30") (pin "2") (pinfunction "Anode_2") (pintype "passive"))
      (node (ref "D31") (pin "2") (pinfunction "Anode_2") (pintype "passive"))
      (node (ref "D32") (pin "2") (pinfunction "Anode_2") (pintype "passive"))
      (node (ref "D33") (pin "2") (pinfunction "Anode_2") (pintype "passive"))
      (node (ref "D34") (pin "2") (pinfunction "Anode_2") (pintype "passive"))
      (node (ref "D35") (pin "2") (pinfunction "Anode_2") (pintype "passive"))
      (node (ref "D36") (pin "2") (pinfunction "Anode_2") (pintype "passive"))
      (node (ref "FB14") (pin "2") (pinfunction "OUT_2") (pintype "passive"))
    )
    (net (code "5") (name "-6V_PH") (class "Default")
      (node (ref "C94") (pin "1") (pinfunction "OUT_1") (pintype "passive"))
      (node (ref "C95") (pin "1") (pinfunction "OUT_1") (pintype "passive"))
      (node (ref "C98") (pin "2") (pinfunction "OUT_2") (pintype "passive"))
      (node (ref "C99") (pin "2") (pinfunction "OUT_2") (pintype "passive"))
      (node (ref "D28") (pin "1") (pinfunction "Anode_1") (pintype "passive"))
      (node (ref "U15") (pin "5") (pinfunction "EN_5") (pintype "passive"))
      (node (ref "U15") (pin "8") (pinfunction "VIN_8") (pintype "power_in"))
    )
    (net (code "6") (name "/OUT_VUN") (class "Default")
      (node (ref "R48") (pin "2") (pinfunction "A_2") (pintype "passive"))
    )
    (net (code "7") (name "/OUT_VUP") (class "Default")
      (node (ref "R45") (pin "2") (pinfunction "A_2") (pintype "passive"))
    )
    (net (code "8") (name "/OUT_VVN") (class "Default")
      (node (ref "R60") (pin "2") (pinfunction "A_2") (pintype "passive"))
    )
    (net (code "9") (name "/OUT_VVP") (class "Default")
      (node (ref "R57") (pin "2") (pinfunction "A_2") (pintype "passive"))
    )
    (net (code "10") (name "/OUT_VWN") (class "Default")
      (node (ref "R72") (pin "2") (pinfunction "A_2") (pintype "passive"))
    )
    (net (code "11") (name "/OUT_VWP") (class "Default")
      (node (ref "R69") (pin "2") (pinfunction "A_2") (pintype "passive"))
    )
    (net (code "12") (name "/VU") (class "Default")
      (node (ref "FB15") (pin "1") (pinfunction "OUT_1") (pintype "passive"))
    )
    (net (code "13") (name "/VV") (class "Default")
      (node (ref "FB16") (pin "1") (pinfunction "OUT_1") (pintype "passive"))
    )
    (net (code "14") (name "/VW") (class "Default")
      (node (ref "FB17") (pin "1") (pinfunction "OUT_1") (pintype "passive"))
    )
    (net (code "15") (name "GND_LV") (class "Default")
      (node (ref "C106") (pin "2") (pinfunction "OUT_2") (pintype "passive"))
      (node (ref "C108") (pin "2") (pinfunction "OUT_2") (pintype "passive"))
      (node (ref "C111") (pin "2") (pinfunction "OUT_2") (pintype "passive"))
      (node (ref "C113") (pin "2") (pinfunction "OUT_2") (pintype "passive"))
      (node (ref "C116") (pin "2") (pinfunction "OUT_2") (pintype "passive"))
      (node (ref "C118") (pin "2") (pinfunction "OUT_2") (pintype "passive"))
      (node (ref "C85") (pin "1") (pinfunction "1_1") (pintype "passive"))
      (node (ref "C86") (pin "1") (pinfunction "OUT_1") (pintype "passive"))
      (node (ref "C87") (pin "1") (pinfunction "OUT_1") (pintype "passive"))
      (node (ref "C88") (pin "1") (pinfunction "OUT_1") (pintype "passive"))
      (node (ref "U14") (pin "4") (pinfunction "GND_4") (pintype "passive"))
      (node (ref "U14") (pin "5") (pinfunction "GND_5") (pintype "passive"))
      (node (ref "U16") (pin "5") (pinfunction "V-_5") (pintype "passive"))
      (node (ref "U17") (pin "5") (pinfunction "V-_5") (pintype "passive"))
      (node (ref "U18") (pin "5") (pinfunction "V-_5") (pintype "passive"))
    )
    (net (code "16") (name "GND_PH") (class "Default")
      (node (ref "C101") (pin "1") (pinfunction "OUT_1") (pintype "passive"))
      (node (ref "C102") (pin "1") (pinfunction "OUT_1") (pintype "passive"))
      (node (ref "C103") (pin "1") (pinfunction "OUT_1") (pintype "passive"))
      (node (ref "C104") (pin "1") (pinfunction "OUT_1") (pintype "passive"))
      (node (ref "C105") (pin "1") (pinfunction "OUT_1") (pintype "passive"))
      (node (ref "C107") (pin "1") (pinfunction "OUT_1") (pintype "passive"))
      (node (ref "C109") (pin "2") (pinfunction "OUT_2") (pintype "passive"))
      (node (ref "C110") (pin "1") (pinfunction "OUT_1") (pintype "passive"))
      (node (ref "C112") (pin "1") (pinfunction "OUT_1") (pintype "passive"))
      (node (ref "C114") (pin "2") (pinfunction "OUT_2") (pintype "passive"))
      (node (ref "C115") (pin "1") (pinfunction "OUT_1") (pintype "passive"))
      (node (ref "C117") (pin "1") (pinfunction "OUT_1") (pintype "passive"))
      (node (ref "C119") (pin "2") (pinfunction "OUT_2") (pintype "passive"))
      (node (ref "C85") (pin "2") (pinfunction "2_2") (pintype "passive"))
      (node (ref "C89") (pin "1") (pinfunction "OUT_1") (pintype "passive"))
      (node (ref "C90") (pin "1") (pinfunction "OUT_1") (pintype "passive"))
      (node (ref "C91") (pin "1") (pinfunction "OUT_1") (pintype "passive"))
      (node (ref "C92") (pin "1") (pinfunction "OUT_1") (pintype "passive"))
      (node (ref "C93") (pin "1") (pinfunction "OUT_1") (pintype "passive"))
      (node (ref "C94") (pin "2") (pinfunction "OUT_2") (pintype "passive"))
      (node (ref "C95") (pin "2") (pinfunction "OUT_2") (pintype "passive"))
      (node (ref "C96") (pin "1") (pinfunction "OUT_1") (pintype "passive"))
      (node (ref "C97") (pin "1") (pinfunction "OUT_1") (pintype "passive"))
      (node (ref "C98") (pin "1") (pinfunction "OUT_1") (pintype "passive"))
      (node (ref "C99") (pin "1") (pinfunction "OUT_1") (pintype "passive"))
      (node (ref "D27") (pin "2") (pinfunction "Anode_2") (pintype "passive"))
      (node (ref "D30") (pin "1") (pinfunction "Anode_1") (pintype "passive"))
      (node (ref "D32") (pin "C") (pinfunction "Cathode_C") (pintype "passive"))
      (node (ref "D34") (pin "C") (pinfunction "Cathode_C") (pintype "passive"))
      (node (ref "D36") (pin "C") (pinfunction "Cathode_C") (pintype "passive"))
      (node (ref "R37") (pin "1") (pinfunction "A_1") (pintype "passive"))
      (node (ref "R39") (pin "1") (pinfunction "A_1") (pintype "passive"))
      (node (ref "R40") (pin "1") (pinfunction "A_1") (pintype "passive"))
      (node (ref "R52") (pin "2") (pinfunction "A_2") (pintype "passive"))
      (node (ref "R64") (pin "2") (pinfunction "A_2") (pintype "passive"))
      (node (ref "R76") (pin "2") (pinfunction "A_2") (pintype "passive"))
      (node (ref "T4") (pin "4") (pinfunction "1_4") (pintype "passive"))
      (node (ref "U13") (pin "1") (pinfunction "GND_1") (pintype "passive"))
      (node (ref "U15") (pin "3") (pinfunction "NC_3") (pintype "passive"))
      (node (ref "U15") (pin "4") (pinfunction "GND_4") (pintype "power_in"))
      (node (ref "U15") (pin "9") (pinfunction "TPAD_9") (pintype "power_in"))
      (node (ref "U16") (pin "3") (pinfunction "-_3") (pintype "passive"))
      (node (ref "U16") (pin "4") (pinfunction "V-_4") (pintype "passive"))
      (node (ref "U17") (pin "3") (pinfunction "-_3") (pintype "passive"))
      (node (ref "U17") (pin "4") (pinfunction "V-_4") (pintype "passive"))
      (node (ref "U18") (pin "3") (pinfunction "-_3") (pintype "passive"))
      (node (ref "U18") (pin "4") (pinfunction "V-_4") (pintype "passive"))
    )
    (net (code "17") (name "N_HV") (class "Default")
      (node (ref "R46") (pin "1") (pinfunction "A_1") (pintype "passive"))
      (node (ref "R47") (pin "1") (pinfunction "A_1") (pintype "passive"))
      (node (ref "R51") (pin "2") (pinfunction "A_2") (pintype "passive"))
      (node (ref "R58") (pin "1") (pinfunction "A_1") (pintype "passive"))
      (node (ref "R59") (pin "1") (pinfunction "A_1") (pintype "passive"))
      (node (ref "R63") (pin "2") (pinfunction "A_2") (pintype "passive"))
      (node (ref "R70") (pin "1") (pinfunction "A_1") (pintype "passive"))
      (node (ref "R71") (pin "1") (pinfunction "A_1") (pintype "passive"))
      (node (ref "R75") (pin "2") (pinfunction "A_2") (pintype "passive"))
    )
    (net (code "18") (name "Net-(D25-Anode-Pad1)") (class "Default")
      (node (ref "D25") (pin "1") (pinfunction "Anode_1") (pintype "passive"))
      (node (ref "D28") (pin "2") (pinfunction "Anode_2") (pintype "passive"))
      (node (ref "T4") (pin "6") (pinfunction "1_6") (pintype "passive"))
    )
    (net (code "19") (name "Net-(D26-PadK)") (class "Default")
      (node (ref "D26") (pin "K") (pinfunction "K_K") (pintype "passive"))
      (node (ref "R37") (pin "2") (pinfunction "A_2") (pintype "passive"))
    )
    (net (code "20") (name "Net-(D29-PadA)") (class "Default")
      (node (ref "D29") (pin "A") (pinfunction "A_A") (pintype "passive"))
      (node (ref "R39") (pin "2") (pinfunction "A_2") (pintype "passive"))
    )
    (net (code "21") (name "Net-(D31-Cathode)") (class "Default")
      (node (ref "C109") (pin "1") (pinfunction "OUT_1") (pintype "passive"))
      (node (ref "D31") (pin "C") (pinfunction "Cathode_C") (pintype "passive"))
      (node (ref "R41") (pin "1") (pinfunction "A_1") (pintype "passive"))
      (node (ref "R44") (pin "2") (pinfunction "A_2") (pintype "passive"))
      (node (ref "U16") (pin "2") (pinfunction "+_2") (pintype "passive"))
    )
    (net (code "22") (name "Net-(D33-Cathode)") (class "Default")
      (node (ref "C114") (pin "1") (pinfunction "OUT_1") (pintype "passive"))
      (node (ref "D33") (pin "C") (pinfunction "Cathode_C") (pintype "passive"))
      (node (ref "R53") (pin "1") (pinfunction "A_1") (pintype "passive"))
      (node (ref "R56") (pin "2") (pinfunction "A_2") (pintype "passive"))
      (node (ref "U17") (pin "2") (pinfunction "+_2") (pintype "passive"))
    )
    (net (code "23") (name "Net-(D35-Cathode)") (class "Default")
      (node (ref "C119") (pin "1") (pinfunction "OUT_1") (pintype "passive"))
      (node (ref "D35") (pin "C") (pinfunction "Cathode_C") (pintype "passive"))
      (node (ref "R65") (pin "1") (pinfunction "A_1") (pintype "passive"))
      (node (ref "R68") (pin "2") (pinfunction "A_2") (pintype "passive"))
      (node (ref "U18") (pin "2") (pinfunction "+_2") (pintype "passive"))
    )
    (net (code "24") (name "Net-(FB15-OUT-Pad2)") (class "Default")
      (node (ref "FB15") (pin "2") (pinfunction "OUT_2") (pintype "passive"))
      (node (ref "R42") (pin "1") (pinfunction "A_1") (pintype "passive"))
    )
    (net (code "25") (name "Net-(FB16-OUT-Pad2)") (class "Default")
      (node (ref "FB16") (pin "2") (pinfunction "OUT_2") (pintype "passive"))
      (node (ref "R54") (pin "1") (pinfunction "A_1") (pintype "passive"))
    )
    (net (code "26") (name "Net-(FB17-OUT-Pad2)") (class "Default")
      (node (ref "FB17") (pin "2") (pinfunction "OUT_2") (pintype "passive"))
      (node (ref "R66") (pin "1") (pinfunction "A_1") (pintype "passive"))
    )
    (net (code "27") (name "Net-(R42-A-Pad2)") (class "Default")
      (node (ref "R42") (pin "2") (pinfunction "A_2") (pintype "passive"))
      (node (ref "R43") (pin "1") (pinfunction "A_1") (pintype "passive"))
    )
    (net (code "28") (name "Net-(R43-A-Pad2)") (class "Default")
      (node (ref "R43") (pin "2") (pinfunction "A_2") (pintype "passive"))
      (node (ref "R49") (pin "1") (pinfunction "A_1") (pintype "passive"))
    )
    (net (code "29") (name "Net-(R44-A-Pad1)") (class "Default")
      (node (ref "R44") (pin "1") (pinfunction "A_1") (pintype "passive"))
      (node (ref "R46") (pin "2") (pinfunction "A_2") (pintype "passive"))
      (node (ref "R47") (pin "2") (pinfunction "A_2") (pintype "passive"))
      (node (ref "R50") (pin "2") (pinfunction "A_2") (pintype "passive"))
    )
    (net (code "30") (name "Net-(R45-A-Pad1)") (class "Default")
      (node (ref "R45") (pin "1") (pinfunction "A_1") (pintype "passive"))
      (node (ref "U16") (pin "7") (pinfunction "+_7") (pintype "passive"))
    )
    (net (code "31") (name "Net-(R48-A-Pad1)") (class "Default")
      (node (ref "R48") (pin "1") (pinfunction "A_1") (pintype "passive"))
      (node (ref "U16") (pin "6") (pinfunction "-_6") (pintype "passive"))
    )
    (net (code "32") (name "Net-(R49-A-Pad2)") (class "Default")
      (node (ref "R49") (pin "2") (pinfunction "A_2") (pintype "passive"))
      (node (ref "R50") (pin "1") (pinfunction "A_1") (pintype "passive"))
    )
    (net (code "33") (name "Net-(R51-A-Pad1)") (class "Default")
      (node (ref "R51") (pin "1") (pinfunction "A_1") (pintype "passive"))
      (node (ref "R52") (pin "1") (pinfunction "A_1") (pintype "passive"))
    )
    (net (code "34") (name "Net-(R54-A-Pad2)") (class "Default")
      (node (ref "R54") (pin "2") (pinfunction "A_2") (pintype "passive"))
      (node (ref "R55") (pin "1") (pinfunction "A_1") (pintype "passive"))
    )
    (net (code "35") (name "Net-(R55-A-Pad2)") (class "Default")
      (node (ref "R55") (pin "2") (pinfunction "A_2") (pintype "passive"))
      (node (ref "R61") (pin "1") (pinfunction "A_1") (pintype "passive"))
    )
    (net (code "36") (name "Net-(R56-A-Pad1)") (class "Default")
      (node (ref "R56") (pin "1") (pinfunction "A_1") (pintype "passive"))
      (node (ref "R58") (pin "2") (pinfunction "A_2") (pintype "passive"))
      (node (ref "R59") (pin "2") (pinfunction "A_2") (pintype "passive"))
      (node (ref "R62") (pin "2") (pinfunction "A_2") (pintype "passive"))
    )
    (net (code "37") (name "Net-(R57-A-Pad1)") (class "Default")
      (node (ref "R57") (pin "1") (pinfunction "A_1") (pintype "passive"))
      (node (ref "U17") (pin "7") (pinfunction "+_7") (pintype "passive"))
    )
    (net (code "38") (name "Net-(R60-A-Pad1)") (class "Default")
      (node (ref "R60") (pin "1") (pinfunction "A_1") (pintype "passive"))
      (node (ref "U17") (pin "6") (pinfunction "-_6") (pintype "passive"))
    )
    (net (code "39") (name "Net-(R61-A-Pad2)") (class "Default")
      (node (ref "R61") (pin "2") (pinfunction "A_2") (pintype "passive"))
      (node (ref "R62") (pin "1") (pinfunction "A_1") (pintype "passive"))
    )
    (net (code "40") (name "Net-(R63-A-Pad1)") (class "Default")
      (node (ref "R63") (pin "1") (pinfunction "A_1") (pintype "passive"))
      (node (ref "R64") (pin "1") (pinfunction "A_1") (pintype "passive"))
    )
    (net (code "41") (name "Net-(R66-A-Pad2)") (class "Default")
      (node (ref "R66") (pin "2") (pinfunction "A_2") (pintype "passive"))
      (node (ref "R67") (pin "1") (pinfunction "A_1") (pintype "passive"))
    )
    (net (code "42") (name "Net-(R67-A-Pad2)") (class "Default")
      (node (ref "R67") (pin "2") (pinfunction "A_2") (pintype "passive"))
      (node (ref "R73") (pin "1") (pinfunction "A_1") (pintype "passive"))
    )
    (net (code "43") (name "Net-(R68-A-Pad1)") (class "Default")
      (node (ref "R68") (pin "1") (pinfunction "A_1") (pintype "passive"))
      (node (ref "R70") (pin "2") (pinfunction "A_2") (pintype "passive"))
      (node (ref "R71") (pin "2") (pinfunction "A_2") (pintype "passive"))
      (node (ref "R74") (pin "2") (pinfunction "A_2") (pintype "passive"))
    )
    (net (code "44") (name "Net-(R69-A-Pad1)") (class "Default")
      (node (ref "R69") (pin "1") (pinfunction "A_1") (pintype "passive"))
      (node (ref "U18") (pin "7") (pinfunction "+_7") (pintype "passive"))
    )
    (net (code "45") (name "Net-(R72-A-Pad1)") (class "Default")
      (node (ref "R72") (pin "1") (pinfunction "A_1") (pintype "passive"))
      (node (ref "U18") (pin "6") (pinfunction "-_6") (pintype "passive"))
    )
    (net (code "46") (name "Net-(R73-A-Pad2)") (class "Default")
      (node (ref "R73") (pin "2") (pinfunction "A_2") (pintype "passive"))
      (node (ref "R74") (pin "1") (pinfunction "A_1") (pintype "passive"))
    )
    (net (code "47") (name "Net-(R75-A-Pad1)") (class "Default")
      (node (ref "R75") (pin "1") (pinfunction "A_1") (pintype "passive"))
      (node (ref "R76") (pin "1") (pinfunction "A_1") (pintype "passive"))
    )
    (net (code "48") (name "Net-(U13-OUT)") (class "Default")
      (node (ref "C91") (pin "2") (pinfunction "OUT_2") (pintype "passive"))
      (node (ref "FB13") (pin "1") (pinfunction "OUT_1") (pintype "passive"))
      (node (ref "U13") (pin "3") (pinfunction "OUT_3") (pintype "passive"))
    )
    (net (code "49") (name "Net-(U14-D1)") (class "Default")
      (node (ref "T4") (pin "3") (pinfunction "1_3") (pintype "passive"))
      (node (ref "U14") (pin "1") (pinfunction "D1_1") (pintype "passive"))
    )
    (net (code "50") (name "Net-(U14-D2)") (class "Default")
      (node (ref "T4") (pin "1") (pinfunction "1_1") (pintype "passive"))
      (node (ref "U14") (pin "3") (pinfunction "D2_3") (pintype "passive"))
    )
    (net (code "51") (name "Net-(U15-FB)") (class "Default")
      (node (ref "C100") (pin "2") (pinfunction "OUT_2") (pintype "passive"))
      (node (ref "R38") (pin "1") (pinfunction "A_1") (pintype "passive"))
      (node (ref "R40") (pin "2") (pinfunction "A_2") (pintype "passive"))
      (node (ref "U15") (pin "2") (pinfunction "FB_2") (pintype "passive"))
    )
    (net (code "52") (name "Net-(U15-NR{slash}SS)") (class "Default")
      (node (ref "C104") (pin "2") (pinfunction "OUT_2") (pintype "passive"))
      (node (ref "U15") (pin "6") (pinfunction "NR/SS_6") (pintype "power_in"))
    )
    (net (code "53") (name "Net-(U15-OUT)") (class "Default")
      (node (ref "C100") (pin "1") (pinfunction "OUT_1") (pintype "passive"))
      (node (ref "C103") (pin "2") (pinfunction "OUT_2") (pintype "passive"))
      (node (ref "FB14") (pin "1") (pinfunction "OUT_1") (pintype "passive"))
      (node (ref "R38") (pin "2") (pinfunction "A_2") (pintype "passive"))
      (node (ref "U15") (pin "1") (pinfunction "OUT_1") (pintype "passive"))
    )
    (net (code "54") (name "unconnected-(T4-1-Pad5)") (class "Default")
      (node (ref "T4") (pin "5") (pinfunction "1_5") (pintype "passive"))
    )
    (net (code "55") (name "unconnected-(U13-NC-Pad4)") (class "Default")
      (node (ref "U13") (pin "4") (pinfunction "NC_4") (pintype "passive"))
    )
    (net (code "56") (name "unconnected-(U13-NC-Pad5)") (class "Default")
      (node (ref "U13") (pin "5") (pinfunction "NC_5") (pintype "passive"))
    )
    (net (code "57") (name "unconnected-(U15-DNC-Pad7)") (class "Default")
      (node (ref "U15") (pin "7") (pinfunction "DNC_7") (pintype "passive"))
    )
  )
)
